# ir_single_slim.net
KiCad netlist of a schematic drawn in EAGLE
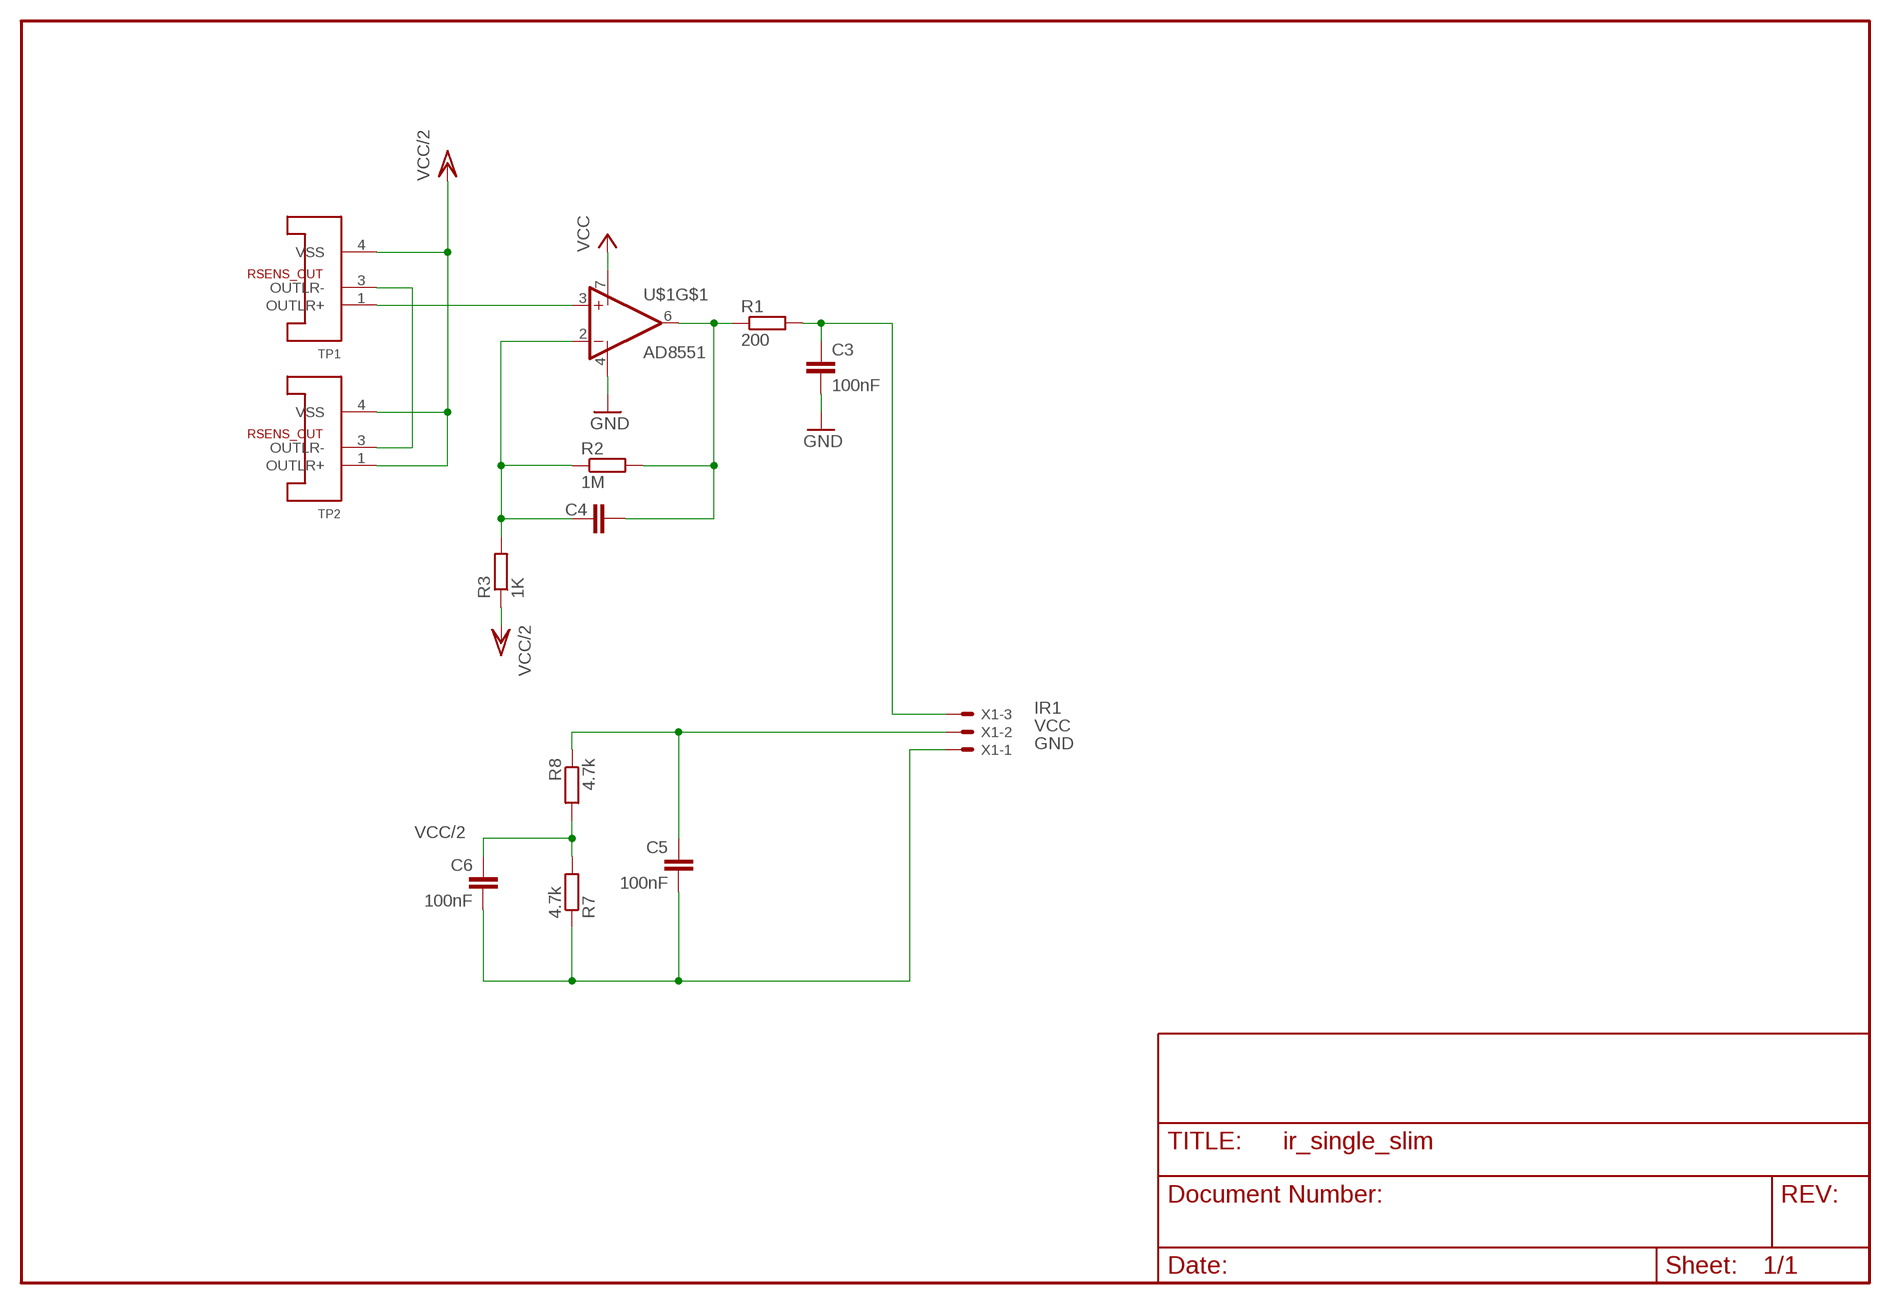
[diagram p0: schematic, sheet 1]

(export (version "E")
  (design (tool "Eeschema 10.0.6"))
  (components
    (comp (ref "C3")
      (value "100nF")
      (footprint "eagle-import:C0603")
      (libsource (lib "eagle-import") (part "C-EUC0603"))
    )
    (comp (ref "C4")
      (value "C-EUC0603")
      (footprint "eagle-import:C0603")
      (libsource (lib "eagle-import") (part "C-EUC0603"))
    )
    (comp (ref "C5")
      (value "100nF")
      (footprint "eagle-import:C0603")
      (libsource (lib "eagle-import") (part "C-EUC0603"))
    )
    (comp (ref "C6")
      (value "100nF")
      (footprint "eagle-import:C0603")
      (libsource (lib "eagle-import") (part "C-EUC0603"))
    )
    (comp (ref "R1")
      (value "200")
      (footprint "eagle-import:R0603")
      (libsource (lib "eagle-import") (part "R-EU_R0603"))
    )
    (comp (ref "R2")
      (value "1M")
      (footprint "eagle-import:R0603")
      (libsource (lib "eagle-import") (part "R-EU_R0603"))
    )
    (comp (ref "R3")
      (value "1K")
      (footprint "eagle-import:R0603")
      (libsource (lib "eagle-import") (part "R-EU_R0603"))
    )
    (comp (ref "R7")
      (value "4.7k")
      (footprint "eagle-import:R0603")
      (libsource (lib "eagle-import") (part "R-EU_R0603"))
    )
    (comp (ref "R8")
      (value "4.7k")
      (footprint "eagle-import:R0603")
      (libsource (lib "eagle-import") (part "R-EU_R0603"))
    )
    (comp (ref "TP1")
      (value "MLX90247V")
      (footprint "eagle-import:TO39")
      (libsource (lib "eagle-import") (part "MLX90247V"))
    )
    (comp (ref "TP2")
      (value "MLX90247V")
      (footprint "eagle-import:TO39")
      (libsource (lib "eagle-import") (part "MLX90247V"))
    )
    (comp (ref "U$1")
      (value "AD8551")
      (footprint "eagle-import:MSOP8")
      (libsource (lib "eagle-import") (part "AD8551"))
    )
    (comp (ref "X1")
      (value "53047-03")
      (footprint "eagle-import:53047-03")
      (libsource (lib "eagle-import") (part "53?-03047"))
    )
  )
  (nets
    (net (code "1") (name "/IR1") (class "Default")
      (node (ref "C3") (pin "1") (pinfunction "1_1") (pintype "passive"))
      (node (ref "R1") (pin "2") (pinfunction "2_2") (pintype "passive"))
      (node (ref "X1") (pin "3") (pinfunction "S_3") (pintype "passive"))
    )
    (net (code "2") (name "GND") (class "Default")
      (node (ref "C3") (pin "2") (pinfunction "2_2") (pintype "passive"))
      (node (ref "C5") (pin "2") (pinfunction "2_2") (pintype "passive"))
      (node (ref "C6") (pin "2") (pinfunction "2_2") (pintype "passive"))
      (node (ref "R7") (pin "1") (pinfunction "1_1") (pintype "passive"))
      (node (ref "U$1") (pin "4") (pinfunction "V-_4") (pintype "power_in"))
      (node (ref "X1") (pin "1") (pinfunction "S_1") (pintype "passive"))
    )
    (net (code "3") (name "Net-(TP1-OUTLR+)") (class "Default")
      (node (ref "TP1") (pin "1") (pinfunction "OUTLR+_1") (pintype "bidirectional"))
      (node (ref "U$1") (pin "3") (pinfunction "+IN_3") (pintype "input"))
    )
    (net (code "4") (name "Net-(TP1-OUTLR-)") (class "Default")
      (node (ref "TP1") (pin "3") (pinfunction "OUTLR-_3") (pintype "bidirectional"))
      (node (ref "TP2") (pin "3") (pinfunction "OUTLR-_3") (pintype "bidirectional"))
    )
    (net (code "5") (name "Net-(U$1A--IN)") (class "Default")
      (node (ref "C4") (pin "1") (pinfunction "1_1") (pintype "passive"))
      (node (ref "R2") (pin "1") (pinfunction "1_1") (pintype "passive"))
      (node (ref "R3") (pin "2") (pinfunction "2_2") (pintype "passive"))
      (node (ref "U$1") (pin "2") (pinfunction "-IN_2") (pintype "input"))
    )
    (net (code "6") (name "Net-(U$1A-OUT)") (class "Default")
      (node (ref "C4") (pin "2") (pinfunction "2_2") (pintype "passive"))
      (node (ref "R1") (pin "1") (pinfunction "1_1") (pintype "passive"))
      (node (ref "R2") (pin "2") (pinfunction "2_2") (pintype "passive"))
      (node (ref "U$1") (pin "6") (pinfunction "OUT_6") (pintype "output"))
    )
    (net (code "7") (name "VCC") (class "Default")
      (node (ref "C5") (pin "1") (pinfunction "1_1") (pintype "passive"))
      (node (ref "R8") (pin "1") (pinfunction "1_1") (pintype "passive"))
      (node (ref "U$1") (pin "7") (pinfunction "V+_7") (pintype "power_in"))
      (node (ref "X1") (pin "2") (pinfunction "S_2") (pintype "passive"))
    )
    (net (code "8") (name "VCC{slash}2") (class "Default")
      (node (ref "C6") (pin "1") (pinfunction "1_1") (pintype "passive"))
      (node (ref "R3") (pin "1") (pinfunction "1_1") (pintype "passive"))
      (node (ref "R7") (pin "2") (pinfunction "2_2") (pintype "passive"))
      (node (ref "R8") (pin "2") (pinfunction "2_2") (pintype "passive"))
      (node (ref "TP1") (pin "4") (pinfunction "VSS_4") (pintype "bidirectional"))
      (node (ref "TP2") (pin "1") (pinfunction "OUTLR+_1") (pintype "bidirectional"))
      (node (ref "TP2") (pin "4") (pinfunction "VSS_4") (pintype "bidirectional"))
    )
  )
)
